# M784.net
KiCad netlist of a schematic drawn in EAGLE
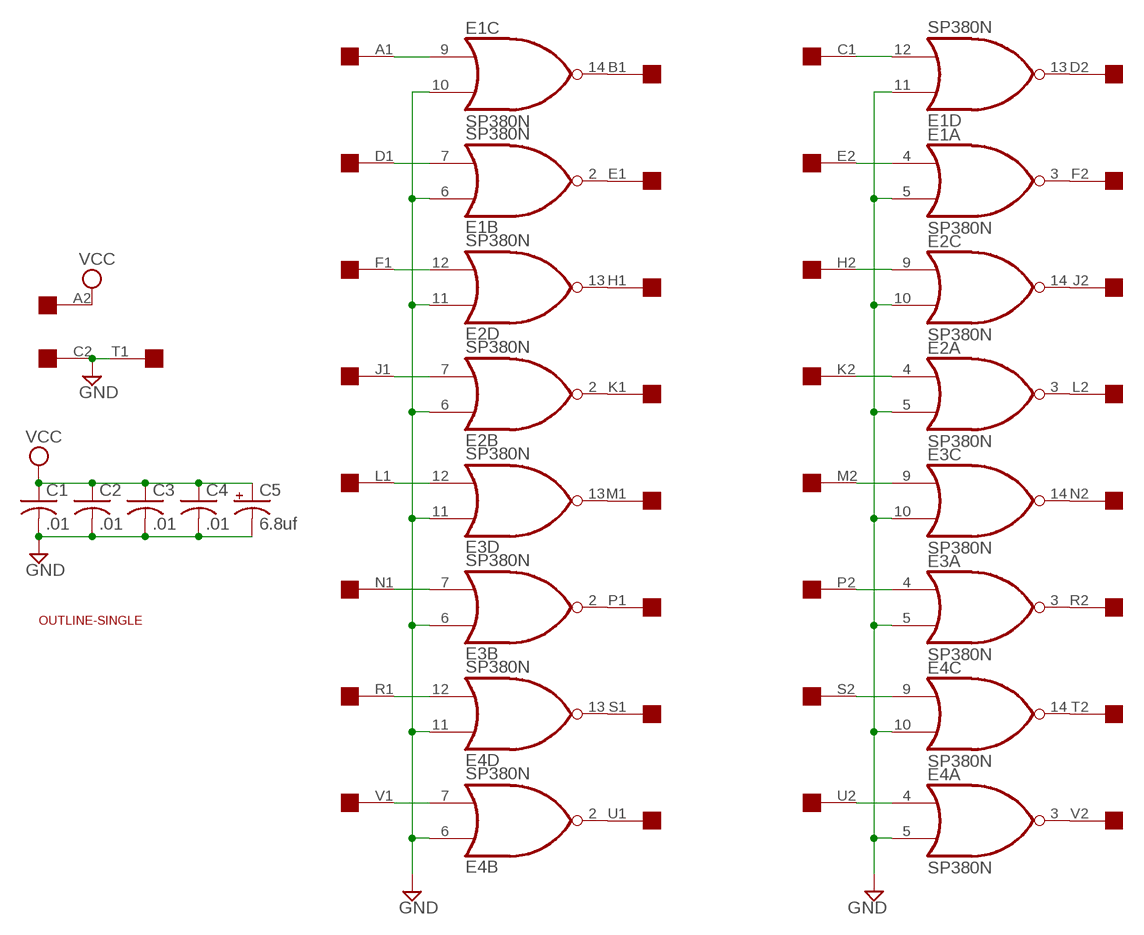
[diagram p0: schematic, sheet 1]

(export (version "E")
  (design (tool "Eeschema 10.0.6"))
  (components
    (comp (ref "C1")
      (value ".01")
      (footprint "eagle-import:C050-025X075")
      (libsource (lib "eagle-import") (part "C-US050-025X075"))
    )
    (comp (ref "C2")
      (value ".01")
      (footprint "eagle-import:C050-025X075")
      (libsource (lib "eagle-import") (part "C-US050-025X075"))
    )
    (comp (ref "C3")
      (value ".01")
      (footprint "eagle-import:C050-025X075")
      (libsource (lib "eagle-import") (part "C-US050-025X075"))
    )
    (comp (ref "C4")
      (value ".01")
      (footprint "eagle-import:C050-025X075")
      (libsource (lib "eagle-import") (part "C-US050-025X075"))
    )
    (comp (ref "C5")
      (value "6.8uf")
      (footprint "eagle-import:E15-5")
      (libsource (lib "eagle-import") (part "CPOL-USE15-5AXIAL"))
    )
    (comp (ref "E1")
      (value "SP380N")
      (footprint "eagle-import:DIL14")
      (libsource (lib "eagle-import") (part "SP380N"))
    )
    (comp (ref "E2")
      (value "SP380N")
      (footprint "eagle-import:DIL14")
      (libsource (lib "eagle-import") (part "SP380N"))
    )
    (comp (ref "E3")
      (value "SP380N")
      (footprint "eagle-import:DIL14")
      (libsource (lib "eagle-import") (part "SP380N"))
    )
    (comp (ref "E4")
      (value "SP380N")
      (footprint "eagle-import:DIL14")
      (libsource (lib "eagle-import") (part "SP380N"))
    )
    (comp (ref "U$1")
      (value "SINGLE")
      (footprint "eagle-import:EDGE-CON2")
      (libsource (lib "eagle-import") (part "SINGLE"))
    )
    (comp (ref "U$2")
      (value "OUTLINE-SINGLE")
      (footprint "eagle-import:SINGLE")
      (libsource (lib "eagle-import") (part "OUTLINE-SINGLE"))
    )
  )
  (nets
    (net (code "1") (name "GND") (class "Default")
      (node (ref "C1") (pin "2") (pinfunction "2_2") (pintype "passive"))
      (node (ref "C2") (pin "2") (pinfunction "2_2") (pintype "passive"))
      (node (ref "C3") (pin "2") (pinfunction "2_2") (pintype "passive"))
      (node (ref "C4") (pin "2") (pinfunction "2_2") (pintype "passive"))
      (node (ref "C5") (pin "-") (pinfunction "-_-") (pintype "passive"))
      (node (ref "E1") (pin "10") (pinfunction "I1_10") (pintype "input"))
      (node (ref "E1") (pin "11") (pinfunction "I0_11") (pintype "input"))
      (node (ref "E1") (pin "5") (pinfunction "I1_5") (pintype "input"))
      (node (ref "E1") (pin "6") (pinfunction "I0_6") (pintype "input"))
      (node (ref "E2") (pin "10") (pinfunction "I1_10") (pintype "input"))
      (node (ref "E2") (pin "11") (pinfunction "I0_11") (pintype "input"))
      (node (ref "E2") (pin "5") (pinfunction "I1_5") (pintype "input"))
      (node (ref "E2") (pin "6") (pinfunction "I0_6") (pintype "input"))
      (node (ref "E3") (pin "10") (pinfunction "I1_10") (pintype "input"))
      (node (ref "E3") (pin "11") (pinfunction "I0_11") (pintype "input"))
      (node (ref "E3") (pin "5") (pinfunction "I1_5") (pintype "input"))
      (node (ref "E3") (pin "6") (pinfunction "I0_6") (pintype "input"))
      (node (ref "E4") (pin "10") (pinfunction "I1_10") (pintype "input"))
      (node (ref "E4") (pin "11") (pinfunction "I0_11") (pintype "input"))
      (node (ref "E4") (pin "5") (pinfunction "I1_5") (pintype "input"))
      (node (ref "E4") (pin "6") (pinfunction "I0_6") (pintype "input"))
      (node (ref "U$1") (pin "C2") (pinfunction "1_C2") (pintype "bidirectional"))
      (node (ref "U$1") (pin "T1") (pinfunction "1_T1") (pintype "bidirectional"))
    )
    (net (code "2") (name "Net-(E1A-I0)") (class "Default")
      (node (ref "E1") (pin "4") (pinfunction "I0_4") (pintype "input"))
      (node (ref "U$1") (pin "E2") (pinfunction "1_E2") (pintype "bidirectional"))
    )
    (net (code "3") (name "Net-(E1A-O)") (class "Default")
      (node (ref "E1") (pin "3") (pinfunction "O_3") (pintype "output"))
      (node (ref "U$1") (pin "F2") (pinfunction "1_F2") (pintype "bidirectional"))
    )
    (net (code "4") (name "Net-(E1B-I1)") (class "Default")
      (node (ref "E1") (pin "7") (pinfunction "I1_7") (pintype "input"))
      (node (ref "U$1") (pin "D1") (pinfunction "1_D1") (pintype "bidirectional"))
    )
    (net (code "5") (name "Net-(E1B-O)") (class "Default")
      (node (ref "E1") (pin "2") (pinfunction "O_2") (pintype "output"))
      (node (ref "U$1") (pin "E1") (pinfunction "1_E1") (pintype "bidirectional"))
    )
    (net (code "6") (name "Net-(E1C-I0)") (class "Default")
      (node (ref "E1") (pin "9") (pinfunction "I0_9") (pintype "input"))
      (node (ref "U$1") (pin "A1") (pinfunction "1_A1") (pintype "bidirectional"))
    )
    (net (code "7") (name "Net-(E1C-O)") (class "Default")
      (node (ref "E1") (pin "14") (pinfunction "O_14") (pintype "output"))
      (node (ref "U$1") (pin "B1") (pinfunction "1_B1") (pintype "bidirectional"))
    )
    (net (code "8") (name "Net-(E1D-I1)") (class "Default")
      (node (ref "E1") (pin "12") (pinfunction "I1_12") (pintype "input"))
      (node (ref "U$1") (pin "C1") (pinfunction "1_C1") (pintype "bidirectional"))
    )
    (net (code "9") (name "Net-(E1D-O)") (class "Default")
      (node (ref "E1") (pin "13") (pinfunction "O_13") (pintype "output"))
      (node (ref "U$1") (pin "D2") (pinfunction "1_D2") (pintype "bidirectional"))
    )
    (net (code "10") (name "Net-(E2A-I0)") (class "Default")
      (node (ref "E2") (pin "4") (pinfunction "I0_4") (pintype "input"))
      (node (ref "U$1") (pin "K2") (pinfunction "1_K2") (pintype "bidirectional"))
    )
    (net (code "11") (name "Net-(E2A-O)") (class "Default")
      (node (ref "E2") (pin "3") (pinfunction "O_3") (pintype "output"))
      (node (ref "U$1") (pin "L2") (pinfunction "1_L2") (pintype "bidirectional"))
    )
    (net (code "12") (name "Net-(E2B-I1)") (class "Default")
      (node (ref "E2") (pin "7") (pinfunction "I1_7") (pintype "input"))
      (node (ref "U$1") (pin "J1") (pinfunction "1_J1") (pintype "bidirectional"))
    )
    (net (code "13") (name "Net-(E2B-O)") (class "Default")
      (node (ref "E2") (pin "2") (pinfunction "O_2") (pintype "output"))
      (node (ref "U$1") (pin "K1") (pinfunction "1_K1") (pintype "bidirectional"))
    )
    (net (code "14") (name "Net-(E2C-I0)") (class "Default")
      (node (ref "E2") (pin "9") (pinfunction "I0_9") (pintype "input"))
      (node (ref "U$1") (pin "H2") (pinfunction "1_H2") (pintype "bidirectional"))
    )
    (net (code "15") (name "Net-(E2C-O)") (class "Default")
      (node (ref "E2") (pin "14") (pinfunction "O_14") (pintype "output"))
      (node (ref "U$1") (pin "J2") (pinfunction "1_J2") (pintype "bidirectional"))
    )
    (net (code "16") (name "Net-(E2D-I1)") (class "Default")
      (node (ref "E2") (pin "12") (pinfunction "I1_12") (pintype "input"))
      (node (ref "U$1") (pin "F1") (pinfunction "1_F1") (pintype "bidirectional"))
    )
    (net (code "17") (name "Net-(E2D-O)") (class "Default")
      (node (ref "E2") (pin "13") (pinfunction "O_13") (pintype "output"))
      (node (ref "U$1") (pin "H1") (pinfunction "1_H1") (pintype "bidirectional"))
    )
    (net (code "18") (name "Net-(E3A-I0)") (class "Default")
      (node (ref "E3") (pin "4") (pinfunction "I0_4") (pintype "input"))
      (node (ref "U$1") (pin "P2") (pinfunction "1_P2") (pintype "bidirectional"))
    )
    (net (code "19") (name "Net-(E3A-O)") (class "Default")
      (node (ref "E3") (pin "3") (pinfunction "O_3") (pintype "output"))
      (node (ref "U$1") (pin "R2") (pinfunction "1_R2") (pintype "bidirectional"))
    )
    (net (code "20") (name "Net-(E3B-I1)") (class "Default")
      (node (ref "E3") (pin "7") (pinfunction "I1_7") (pintype "input"))
      (node (ref "U$1") (pin "N1") (pinfunction "1_N1") (pintype "bidirectional"))
    )
    (net (code "21") (name "Net-(E3B-O)") (class "Default")
      (node (ref "E3") (pin "2") (pinfunction "O_2") (pintype "output"))
      (node (ref "U$1") (pin "P1") (pinfunction "1_P1") (pintype "bidirectional"))
    )
    (net (code "22") (name "Net-(E3C-I0)") (class "Default")
      (node (ref "E3") (pin "9") (pinfunction "I0_9") (pintype "input"))
      (node (ref "U$1") (pin "M2") (pinfunction "1_M2") (pintype "bidirectional"))
    )
    (net (code "23") (name "Net-(E3C-O)") (class "Default")
      (node (ref "E3") (pin "14") (pinfunction "O_14") (pintype "output"))
      (node (ref "U$1") (pin "N2") (pinfunction "1_N2") (pintype "bidirectional"))
    )
    (net (code "24") (name "Net-(E3D-I1)") (class "Default")
      (node (ref "E3") (pin "12") (pinfunction "I1_12") (pintype "input"))
      (node (ref "U$1") (pin "L1") (pinfunction "1_L1") (pintype "bidirectional"))
    )
    (net (code "25") (name "Net-(E3D-O)") (class "Default")
      (node (ref "E3") (pin "13") (pinfunction "O_13") (pintype "output"))
      (node (ref "U$1") (pin "M1") (pinfunction "1_M1") (pintype "bidirectional"))
    )
    (net (code "26") (name "Net-(E4A-I0)") (class "Default")
      (node (ref "E4") (pin "4") (pinfunction "I0_4") (pintype "input"))
      (node (ref "U$1") (pin "U2") (pinfunction "1_U2") (pintype "bidirectional"))
    )
    (net (code "27") (name "Net-(E4A-O)") (class "Default")
      (node (ref "E4") (pin "3") (pinfunction "O_3") (pintype "output"))
      (node (ref "U$1") (pin "V2") (pinfunction "1_V2") (pintype "bidirectional"))
    )
    (net (code "28") (name "Net-(E4B-I1)") (class "Default")
      (node (ref "E4") (pin "7") (pinfunction "I1_7") (pintype "input"))
      (node (ref "U$1") (pin "V1") (pinfunction "1_V1") (pintype "bidirectional"))
    )
    (net (code "29") (name "Net-(E4B-O)") (class "Default")
      (node (ref "E4") (pin "2") (pinfunction "O_2") (pintype "output"))
      (node (ref "U$1") (pin "U1") (pinfunction "1_U1") (pintype "bidirectional"))
    )
    (net (code "30") (name "Net-(E4C-I0)") (class "Default")
      (node (ref "E4") (pin "9") (pinfunction "I0_9") (pintype "input"))
      (node (ref "U$1") (pin "S2") (pinfunction "1_S2") (pintype "bidirectional"))
    )
    (net (code "31") (name "Net-(E4C-O)") (class "Default")
      (node (ref "E4") (pin "14") (pinfunction "O_14") (pintype "output"))
      (node (ref "U$1") (pin "T2") (pinfunction "1_T2") (pintype "bidirectional"))
    )
    (net (code "32") (name "Net-(E4D-I1)") (class "Default")
      (node (ref "E4") (pin "12") (pinfunction "I1_12") (pintype "input"))
      (node (ref "U$1") (pin "R1") (pinfunction "1_R1") (pintype "bidirectional"))
    )
    (net (code "33") (name "Net-(E4D-O)") (class "Default")
      (node (ref "E4") (pin "13") (pinfunction "O_13") (pintype "output"))
      (node (ref "U$1") (pin "S1") (pinfunction "1_S1") (pintype "bidirectional"))
    )
    (net (code "34") (name "VCC") (class "Default")
      (node (ref "C1") (pin "1") (pinfunction "1_1") (pintype "passive"))
      (node (ref "C2") (pin "1") (pinfunction "1_1") (pintype "passive"))
      (node (ref "C3") (pin "1") (pinfunction "1_1") (pintype "passive"))
      (node (ref "C4") (pin "1") (pinfunction "1_1") (pintype "passive"))
      (node (ref "C5") (pin "+") (pinfunction "+_+") (pintype "passive"))
      (node (ref "U$1") (pin "A2") (pinfunction "1_A2") (pintype "bidirectional"))
    )
  )
)
